# MCU.net
KiCad netlist of a schematic drawn in Altium Designer
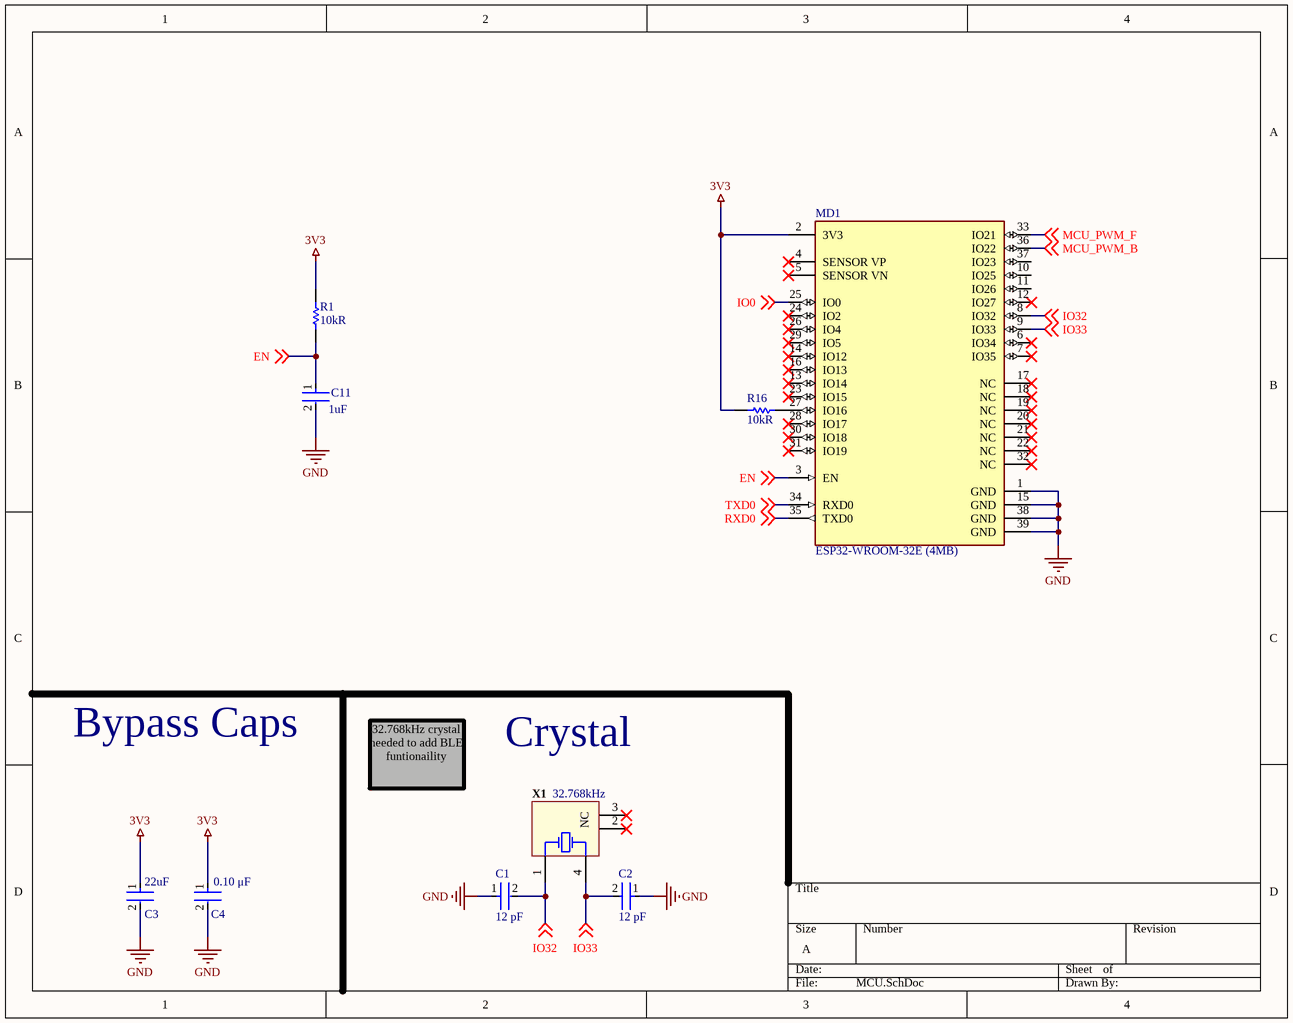
[diagram p0: MCU.SchDoc]

(export (version "E")
  (design (tool "Eeschema 10.0.6"))
  (components
    (comp (ref "C1")
      (value "12 pF")
      (footprint "FP-C0805C-DN-MFG")
      (description "CAP CER 12PF 50V C0G/NP0 0805")
      (fields (field (name "MANUFACTURER") "KEMET") (field (name "TOLERANCE") "0.05"))
      (libsource (lib "Altium Content Vault") (part "b4654b650e69147ec39a6b967a45e02"))
    )
    (comp (ref "C2")
      (value "12 pF")
      (footprint "FP-C0805C-DN-MFG")
      (description "CAP CER 12PF 50V C0G/NP0 0805")
      (fields (field (name "MANUFACTURER") "KEMET") (field (name "TOLERANCE") "0.05"))
      (libsource (lib "Altium Content Vault") (part "b4654b650e69147ec39a6b967a45e02"))
    )
    (comp (ref "C3")
      (value "GRM21BR60J226ME39L")
      (footprint "FP-GRM21B-0_15-MFG")
      (description "Chip Multilayer Ceramic Capacitors for General Purpose, 0805, 22uF, X5R, 15%, 20%, 6.3V")
      (fields
        (field (name "VOLTAGE") "6.3V")
        (field (name "TOLERANCE") "20%")
        (field (name "CAPACITANCE") "22uF")
      )
      (libsource (lib "Altium Content Vault") (part "b4654b650e69147ec39a6b967a45e02"))
    )
    (comp (ref "C4")
      (value "0.10 μF")
      (footprint "FP-C1206C-EB-MFG")
      (description "CAP CER 0.1UF 100V X7R 1206")
      (fields
        (field (name "TOLERANCE") "0.1")
        (field (name "OCTOPART") "https://octopart.com/c1206c104k1ractu-kemet-89521")
      )
      (libsource (lib "Altium Content Vault") (part "b4654b650e69147ec39a6b967a45e02"))
    )
    (comp (ref "C11")
      (value "CL21B105KOFNNNE")
      (footprint "FP-CL21-IPC_A")
      (description "CL21 Series 0805 1uF 16V ±10% Tolerance X7R Multilayer Ceramic Chip Capacitor")
      (fields
        (field (name "CAPACITANCE") "1uF")
        (field (name "TOLERANCE") "10%")
        (field (name "VOLTAGE") "16V")
      )
      (libsource (lib "Altium Content Vault") (part "b4654b650e69147ec39a6b967a45e02"))
    )
    (comp (ref "MD1")
      (value "ESP32-WROOM-32E (4MB)")
      (footprint "FP-ESP32-WROOM-32E_4MB-MFG")
      (description "RX TXRX MOD WIFI TRACE ANT SMD")
      (libsource (lib "Altium Content Vault") (part "7f842c3463a9561e2f6f9fdcd687e0f"))
    )
    (comp (ref "R1")
      (value "10kR")
      (footprint "RESC2013X60X35NL10T20")
      (description "Chip Resistor, 10 KOhm, +/- 1%, 0.125 W, -55 to 155 degC, 0805 (2012 Metric), RoHS, Tape and Reel")
      (fields
        (field (name "MANUFACTURER") "Yageo")
        (field (name "MANUFACTURER PART NUMBER") "RC0805FR-0710KL")
      )
      (libsource (lib "Altium Content Vault") (part "RES-2"))
    )
    (comp (ref "R16")
      (value "10kR")
      (footprint "RESC2013X60X35NL10T20")
      (description "Chip Resistor, 10 KOhm, +/- 1%, 0.125 W, -55 to 155 degC, 0805 (2012 Metric), RoHS, Tape and Reel")
      (fields
        (field (name "MANUFACTURER") "Yageo")
        (field (name "MANUFACTURER PART NUMBER") "RC0805FR-0710KL")
      )
      (libsource (lib "Altium Content Vault") (part "RES-2"))
    )
    (comp (ref "X1")
      (value "ABS25-32.768KHZ-6-T")
      (footprint "ABRA-ABS25-4_V")
      (fields
        (field (name "FREQUENCY") "32.768kHz")
        (field (name "TOLERANCE") "20PPM")
        (field (name "MANUFACTURER") "Abracon")
      )
      (libsource (lib "Altium Content Vault") (part "ABRA-XTAL_1-4-4"))
    )
  )
  (nets
    (net (code "1") (name "3V3") (class "Default")
      (node (ref "C3") (pin "1") (pinfunction "1_1") (pintype "passive"))
      (node (ref "C4") (pin "1") (pinfunction "1_1") (pintype "passive"))
      (node (ref "MD1") (pin "2") (pinfunction "3V3_2") (pintype "power_in"))
      (node (ref "R1") (pin "1") (pinfunction "1_1") (pintype "passive"))
      (node (ref "R16") (pin "2") (pinfunction "2_2") (pintype "passive"))
    )
    (net (code "2") (name "EN") (class "Default")
      (node (ref "C11") (pin "1") (pinfunction "1_1") (pintype "passive"))
      (node (ref "MD1") (pin "3") (pinfunction "EN_3") (pintype "input"))
      (node (ref "R1") (pin "2") (pinfunction "2_2") (pintype "passive"))
    )
    (net (code "3") (name "GND") (class "Default")
      (node (ref "C1") (pin "1") (pinfunction "1_1") (pintype "passive"))
      (node (ref "C11") (pin "2") (pinfunction "2_2") (pintype "passive"))
      (node (ref "C2") (pin "1") (pinfunction "1_1") (pintype "passive"))
      (node (ref "C3") (pin "2") (pinfunction "2_2") (pintype "passive"))
      (node (ref "C4") (pin "2") (pinfunction "2_2") (pintype "passive"))
      (node (ref "MD1") (pin "1") (pinfunction "GND_1") (pintype "power_in"))
      (node (ref "MD1") (pin "15") (pinfunction "GND_15") (pintype "power_in"))
      (node (ref "MD1") (pin "38") (pinfunction "GND_38") (pintype "power_in"))
      (node (ref "MD1") (pin "39") (pinfunction "GND_39") (pintype "power_in"))
    )
    (net (code "4") (name "IO0") (class "Default")
      (node (ref "MD1") (pin "25") (pinfunction "IO0_25") (pintype "bidirectional"))
    )
    (net (code "5") (name "IO32") (class "Default")
      (node (ref "C1") (pin "2") (pinfunction "2_2") (pintype "passive"))
      (node (ref "MD1") (pin "8") (pinfunction "IO32_8") (pintype "bidirectional"))
      (node (ref "X1") (pin "1") (pinfunction "X1_1") (pintype "passive"))
    )
    (net (code "6") (name "IO33") (class "Default")
      (node (ref "C2") (pin "2") (pinfunction "2_2") (pintype "passive"))
      (node (ref "MD1") (pin "9") (pinfunction "IO33_9") (pintype "bidirectional"))
      (node (ref "X1") (pin "4") (pinfunction "X2_4") (pintype "passive"))
    )
    (net (code "7") (name "MCU_PWM_B") (class "Default")
      (node (ref "MD1") (pin "36") (pinfunction "IO22_36") (pintype "bidirectional"))
    )
    (net (code "8") (name "MCU_PWM_F") (class "Default")
      (node (ref "MD1") (pin "33") (pinfunction "IO21_33") (pintype "bidirectional"))
    )
    (net (code "9") (name "Net-(MD1-IO16)") (class "Default")
      (node (ref "MD1") (pin "27") (pinfunction "IO16_27") (pintype "bidirectional"))
      (node (ref "R16") (pin "1") (pinfunction "1_1") (pintype "passive"))
    )
    (net (code "10") (name "RXD0") (class "Default")
      (node (ref "MD1") (pin "35") (pinfunction "TXD0_35") (pintype "output"))
    )
    (net (code "11") (name "TXD0") (class "Default")
      (node (ref "MD1") (pin "34") (pinfunction "RXD0_34") (pintype "input"))
    )
    (net (code "12") (name "unconnected-(MD1-IO2-Pad24)") (class "Default")
      (node (ref "MD1") (pin "24") (pinfunction "IO2_24") (pintype "bidirectional+no_connect"))
    )
    (net (code "13") (name "unconnected-(MD1-IO4-Pad26)") (class "Default")
      (node (ref "MD1") (pin "26") (pinfunction "IO4_26") (pintype "bidirectional+no_connect"))
    )
    (net (code "14") (name "unconnected-(MD1-IO5-Pad29)") (class "Default")
      (node (ref "MD1") (pin "29") (pinfunction "IO5_29") (pintype "bidirectional+no_connect"))
    )
    (net (code "15") (name "unconnected-(MD1-IO12-Pad14)") (class "Default")
      (node (ref "MD1") (pin "14") (pinfunction "IO12_14") (pintype "bidirectional+no_connect"))
    )
    (net (code "16") (name "unconnected-(MD1-IO13-Pad16)") (class "Default")
      (node (ref "MD1") (pin "16") (pinfunction "IO13_16") (pintype "bidirectional+no_connect"))
    )
    (net (code "17") (name "unconnected-(MD1-IO14-Pad13)") (class "Default")
      (node (ref "MD1") (pin "13") (pinfunction "IO14_13") (pintype "bidirectional+no_connect"))
    )
    (net (code "18") (name "unconnected-(MD1-IO15-Pad23)") (class "Default")
      (node (ref "MD1") (pin "23") (pinfunction "IO15_23") (pintype "bidirectional+no_connect"))
    )
    (net (code "19") (name "unconnected-(MD1-IO17-Pad28)") (class "Default")
      (node (ref "MD1") (pin "28") (pinfunction "IO17_28") (pintype "bidirectional+no_connect"))
    )
    (net (code "20") (name "unconnected-(MD1-IO18-Pad30)") (class "Default")
      (node (ref "MD1") (pin "30") (pinfunction "IO18_30") (pintype "bidirectional+no_connect"))
    )
    (net (code "21") (name "unconnected-(MD1-IO19-Pad31)") (class "Default")
      (node (ref "MD1") (pin "31") (pinfunction "IO19_31") (pintype "bidirectional+no_connect"))
    )
    (net (code "22") (name "unconnected-(MD1-IO23-Pad37)") (class "Default")
      (node (ref "MD1") (pin "37") (pinfunction "IO23_37") (pintype "bidirectional"))
    )
    (net (code "23") (name "unconnected-(MD1-IO25-Pad10)") (class "Default")
      (node (ref "MD1") (pin "10") (pinfunction "IO25_10") (pintype "bidirectional"))
    )
    (net (code "24") (name "unconnected-(MD1-IO26-Pad11)") (class "Default")
      (node (ref "MD1") (pin "11") (pinfunction "IO26_11") (pintype "bidirectional"))
    )
    (net (code "25") (name "unconnected-(MD1-IO27-Pad12)") (class "Default")
      (node (ref "MD1") (pin "12") (pinfunction "IO27_12") (pintype "bidirectional+no_connect"))
    )
    (net (code "26") (name "unconnected-(MD1-IO34-Pad6)") (class "Default")
      (node (ref "MD1") (pin "6") (pinfunction "IO34_6") (pintype "bidirectional+no_connect"))
    )
    (net (code "27") (name "unconnected-(MD1-IO35-Pad7)") (class "Default")
      (node (ref "MD1") (pin "7") (pinfunction "IO35_7") (pintype "bidirectional+no_connect"))
    )
    (net (code "28") (name "unconnected-(MD1-NC-Pad17)") (class "Default")
      (node (ref "MD1") (pin "17") (pinfunction "NC_17") (pintype "passive+no_connect"))
    )
    (net (code "29") (name "unconnected-(MD1-NC-Pad18)") (class "Default")
      (node (ref "MD1") (pin "18") (pinfunction "NC_18") (pintype "passive+no_connect"))
    )
    (net (code "30") (name "unconnected-(MD1-NC-Pad19)") (class "Default")
      (node (ref "MD1") (pin "19") (pinfunction "NC_19") (pintype "passive+no_connect"))
    )
    (net (code "31") (name "unconnected-(MD1-NC-Pad20)") (class "Default")
      (node (ref "MD1") (pin "20") (pinfunction "NC_20") (pintype "passive+no_connect"))
    )
    (net (code "32") (name "unconnected-(MD1-NC-Pad21)") (class "Default")
      (node (ref "MD1") (pin "21") (pinfunction "NC_21") (pintype "passive+no_connect"))
    )
    (net (code "33") (name "unconnected-(MD1-NC-Pad22)") (class "Default")
      (node (ref "MD1") (pin "22") (pinfunction "NC_22") (pintype "passive+no_connect"))
    )
    (net (code "34") (name "unconnected-(MD1-NC-Pad32)") (class "Default")
      (node (ref "MD1") (pin "32") (pinfunction "NC_32") (pintype "passive+no_connect"))
    )
    (net (code "35") (name "unconnected-(MD1-SENSOR_VN-Pad5)") (class "Default")
      (node (ref "MD1") (pin "5") (pinfunction "SENSOR_VN_5") (pintype "passive+no_connect"))
    )
    (net (code "36") (name "unconnected-(MD1-SENSOR_VP-Pad4)") (class "Default")
      (node (ref "MD1") (pin "4") (pinfunction "SENSOR_VP_4") (pintype "passive+no_connect"))
    )
    (net (code "37") (name "unconnected-(X1-NC-Pad2)") (class "Default")
      (node (ref "X1") (pin "2") (pinfunction "NC_2") (pintype "passive+no_connect"))
    )
    (net (code "38") (name "unconnected-(X1-NC-Pad3)") (class "Default")
      (node (ref "X1") (pin "3") (pinfunction "NC_3") (pintype "passive+no_connect"))
    )
  )
)
